# E17-PDU-6-LOAD_2.net
KiCad netlist of a schematic drawn in Altium Designer
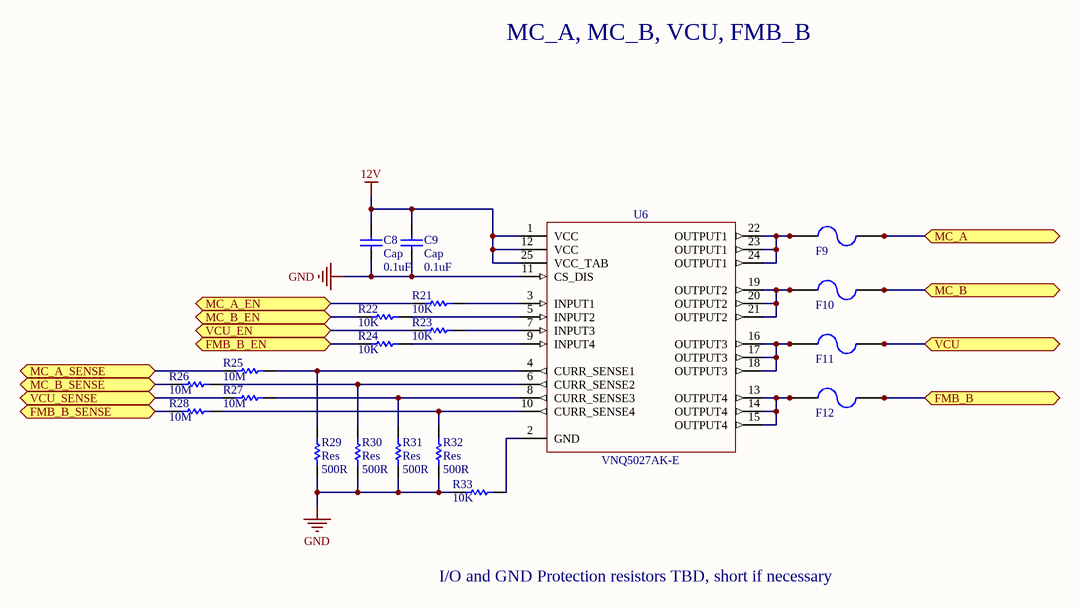
[diagram p0: E17-PDU-6-LOAD_2.SchDoc]

(export (version "E")
  (design (tool "Eeschema 10.0.6"))
  (components
    (comp (ref "C8")
      (value "Cap")
      (footprint "C0805")
      (description "Capacitor")
      (fields (field (name "ALTIUM_VALUE") "0.1uF") (field (name "PUBLISHER") "Altium Limited"))
      (libsource (lib "Capacitors") (part "Cap"))
    )
    (comp (ref "C9")
      (value "Cap")
      (footprint "C0805")
      (description "Capacitor")
      (fields (field (name "ALTIUM_VALUE") "0.1uF") (field (name "PUBLISHER") "Altium Limited"))
      (libsource (lib "Capacitors") (part "Cap"))
    )
    (comp (ref "F9")
      (value "BK-6013")
      (footprint "BK-6013")
      (description "FUSE HOLDER BLADE PCB")
      (libsource (lib "Fuses") (part "BK-6013"))
    )
    (comp (ref "F10")
      (value "BK-6013")
      (footprint "BK-6013")
      (description "FUSE HOLDER BLADE PCB")
      (libsource (lib "Fuses") (part "BK-6013"))
    )
    (comp (ref "F11")
      (value "BK-6013")
      (footprint "BK-6013")
      (description "FUSE HOLDER BLADE PCB")
      (libsource (lib "Fuses") (part "BK-6013"))
    )
    (comp (ref "F12")
      (value "BK-6013")
      (footprint "BK-6013")
      (description "FUSE HOLDER BLADE PCB")
      (libsource (lib "Fuses") (part "BK-6013"))
    )
    (comp (ref "R21")
      (value "10K")
      (footprint "2012[0805]")
      (description "Surface Mount Resistor")
      (fields (field (name "Comment") "Res") (field (name "PUBLISHER") "Altium Limited"))
      (libsource (lib "Resistors") (part "Res"))
    )
    (comp (ref "R22")
      (value "10K")
      (footprint "2012[0805]")
      (description "Surface Mount Resistor")
      (fields (field (name "Comment") "Res") (field (name "PUBLISHER") "Altium Limited"))
      (libsource (lib "Resistors") (part "Res"))
    )
    (comp (ref "R23")
      (value "10K")
      (footprint "2012[0805]")
      (description "Surface Mount Resistor")
      (fields (field (name "Comment") "Res") (field (name "PUBLISHER") "Altium Limited"))
      (libsource (lib "Resistors") (part "Res"))
    )
    (comp (ref "R24")
      (value "10K")
      (footprint "2012[0805]")
      (description "Surface Mount Resistor")
      (fields (field (name "Comment") "Res") (field (name "PUBLISHER") "Altium Limited"))
      (libsource (lib "Resistors") (part "Res"))
    )
    (comp (ref "R25")
      (value "10M")
      (footprint "2012[0805]")
      (description "Surface Mount Resistor")
      (fields (field (name "Comment") "Res") (field (name "PUBLISHER") "Altium Limited"))
      (libsource (lib "Resistors") (part "Res"))
    )
    (comp (ref "R26")
      (value "10M")
      (footprint "2012[0805]")
      (description "Surface Mount Resistor")
      (fields (field (name "Comment") "Res") (field (name "PUBLISHER") "Altium Limited"))
      (libsource (lib "Resistors") (part "Res"))
    )
    (comp (ref "R27")
      (value "10M")
      (footprint "2012[0805]")
      (description "Surface Mount Resistor")
      (fields (field (name "Comment") "Res") (field (name "PUBLISHER") "Altium Limited"))
      (libsource (lib "Resistors") (part "Res"))
    )
    (comp (ref "R28")
      (value "10M")
      (footprint "2012[0805]")
      (description "Surface Mount Resistor")
      (fields (field (name "Comment") "Res") (field (name "PUBLISHER") "Altium Limited"))
      (libsource (lib "Resistors") (part "Res"))
    )
    (comp (ref "R29")
      (value "Res")
      (footprint "2012[0805]")
      (description "Surface Mount Resistor")
      (fields (field (name "ALTIUM_VALUE") "500R") (field (name "PUBLISHER") "Altium Limited"))
      (libsource (lib "Resistors") (part "Res"))
    )
    (comp (ref "R30")
      (value "Res")
      (footprint "2012[0805]")
      (description "Surface Mount Resistor")
      (fields (field (name "ALTIUM_VALUE") "500R") (field (name "PUBLISHER") "Altium Limited"))
      (libsource (lib "Resistors") (part "Res"))
    )
    (comp (ref "R31")
      (value "Res")
      (footprint "2012[0805]")
      (description "Surface Mount Resistor")
      (fields (field (name "ALTIUM_VALUE") "500R") (field (name "PUBLISHER") "Altium Limited"))
      (libsource (lib "Resistors") (part "Res"))
    )
    (comp (ref "R32")
      (value "Res")
      (footprint "2012[0805]")
      (description "Surface Mount Resistor")
      (fields (field (name "ALTIUM_VALUE") "500R") (field (name "PUBLISHER") "Altium Limited"))
      (libsource (lib "Resistors") (part "Res"))
    )
    (comp (ref "R33")
      (value "10K")
      (footprint "2012[0805]")
      (description "Surface Mount Resistor")
      (fields (field (name "Comment") "Res") (field (name "PUBLISHER") "Altium Limited"))
      (libsource (lib "Resistors") (part "Res"))
    )
    (comp (ref "U6")
      (value "U_VNQ5027AK-E")
      (footprint "PowerSSO-24")
      (description "LOAD CHANNEL HIGH SIDE 42 A 4 Channel")
      (fields (field (name "MFG") "STmicroelectronics") (field (name "MFG_PN") "VNQ5027AK-E"))
      (libsource (lib "Transistors") (part "U_VNQ5027AK-E"))
    )
  )
  (nets
    (net (code "1") (name "/FMB_B") (class "Default")
      (node (ref "F12") (pin "3") (pinfunction "3_3") (pintype "passive"))
      (node (ref "F12") (pin "4") (pinfunction "4_4") (pintype "passive"))
    )
    (net (code "2") (name "/FMB_B_EN") (class "Default")
      (node (ref "R24") (pin "2") (pinfunction "2_2") (pintype "passive"))
    )
    (net (code "3") (name "/FMB_B_SENSE") (class "Default")
      (node (ref "R28") (pin "2") (pinfunction "2_2") (pintype "passive"))
    )
    (net (code "4") (name "/MC_A") (class "Default")
      (node (ref "F9") (pin "3") (pinfunction "3_3") (pintype "passive"))
      (node (ref "F9") (pin "4") (pinfunction "4_4") (pintype "passive"))
    )
    (net (code "5") (name "/MC_A_EN") (class "Default")
      (node (ref "R21") (pin "2") (pinfunction "2_2") (pintype "passive"))
    )
    (net (code "6") (name "/MC_A_SENSE") (class "Default")
      (node (ref "R25") (pin "2") (pinfunction "2_2") (pintype "passive"))
    )
    (net (code "7") (name "/MC_B") (class "Default")
      (node (ref "F10") (pin "3") (pinfunction "3_3") (pintype "passive"))
      (node (ref "F10") (pin "4") (pinfunction "4_4") (pintype "passive"))
    )
    (net (code "8") (name "/MC_B_EN") (class "Default")
      (node (ref "R22") (pin "2") (pinfunction "2_2") (pintype "passive"))
    )
    (net (code "9") (name "/MC_B_SENSE") (class "Default")
      (node (ref "R26") (pin "2") (pinfunction "2_2") (pintype "passive"))
    )
    (net (code "10") (name "/VCU") (class "Default")
      (node (ref "F11") (pin "3") (pinfunction "3_3") (pintype "passive"))
      (node (ref "F11") (pin "4") (pinfunction "4_4") (pintype "passive"))
    )
    (net (code "11") (name "/VCU_EN") (class "Default")
      (node (ref "R23") (pin "2") (pinfunction "2_2") (pintype "passive"))
    )
    (net (code "12") (name "/VCU_SENSE") (class "Default")
      (node (ref "R27") (pin "2") (pinfunction "2_2") (pintype "passive"))
    )
    (net (code "13") (name "12V") (class "Default")
      (node (ref "C8") (pin "2") (pinfunction "2_2") (pintype "passive"))
      (node (ref "C9") (pin "2") (pinfunction "2_2") (pintype "passive"))
      (node (ref "U6") (pin "1") (pinfunction "VCC_1") (pintype "power_in"))
      (node (ref "U6") (pin "12") (pinfunction "VCC_12") (pintype "power_in"))
      (node (ref "U6") (pin "25") (pinfunction "VCC_TAB_25") (pintype "power_in"))
    )
    (net (code "14") (name "GND") (class "Default")
      (node (ref "C8") (pin "1") (pinfunction "1_1") (pintype "passive"))
      (node (ref "C9") (pin "1") (pinfunction "1_1") (pintype "passive"))
      (node (ref "R29") (pin "1") (pinfunction "1_1") (pintype "passive"))
      (node (ref "R30") (pin "1") (pinfunction "1_1") (pintype "passive"))
      (node (ref "R31") (pin "1") (pinfunction "1_1") (pintype "passive"))
      (node (ref "R32") (pin "1") (pinfunction "1_1") (pintype "passive"))
      (node (ref "R33") (pin "2") (pinfunction "2_2") (pintype "passive"))
      (node (ref "U6") (pin "11") (pinfunction "CS_DIS_11") (pintype "input"))
    )
    (net (code "15") (name "Net-(F9-Pad1)") (class "Default")
      (node (ref "F9") (pin "1") (pinfunction "1_1") (pintype "passive"))
      (node (ref "F9") (pin "2") (pinfunction "2_2") (pintype "passive"))
      (node (ref "U6") (pin "22") (pinfunction "OUTPUT1_22") (pintype "output"))
      (node (ref "U6") (pin "23") (pinfunction "OUTPUT1_23") (pintype "output"))
      (node (ref "U6") (pin "24") (pinfunction "OUTPUT1_24") (pintype "output"))
    )
    (net (code "16") (name "Net-(F10-Pad1)") (class "Default")
      (node (ref "F10") (pin "1") (pinfunction "1_1") (pintype "passive"))
      (node (ref "F10") (pin "2") (pinfunction "2_2") (pintype "passive"))
      (node (ref "U6") (pin "19") (pinfunction "OUTPUT2_19") (pintype "output"))
      (node (ref "U6") (pin "20") (pinfunction "OUTPUT2_20") (pintype "output"))
      (node (ref "U6") (pin "21") (pinfunction "OUTPUT2_21") (pintype "output"))
    )
    (net (code "17") (name "Net-(F11-Pad1)") (class "Default")
      (node (ref "F11") (pin "1") (pinfunction "1_1") (pintype "passive"))
      (node (ref "F11") (pin "2") (pinfunction "2_2") (pintype "passive"))
      (node (ref "U6") (pin "16") (pinfunction "OUTPUT3_16") (pintype "output"))
      (node (ref "U6") (pin "17") (pinfunction "OUTPUT3_17") (pintype "output"))
      (node (ref "U6") (pin "18") (pinfunction "OUTPUT3_18") (pintype "output"))
    )
    (net (code "18") (name "Net-(F12-Pad1)") (class "Default")
      (node (ref "F12") (pin "1") (pinfunction "1_1") (pintype "passive"))
      (node (ref "F12") (pin "2") (pinfunction "2_2") (pintype "passive"))
      (node (ref "U6") (pin "13") (pinfunction "OUTPUT4_13") (pintype "output"))
      (node (ref "U6") (pin "14") (pinfunction "OUTPUT4_14") (pintype "output"))
      (node (ref "U6") (pin "15") (pinfunction "OUTPUT4_15") (pintype "output"))
    )
    (net (code "19") (name "Net-(U6-CURR_SENSE1)") (class "Default")
      (node (ref "R25") (pin "1") (pinfunction "1_1") (pintype "passive"))
      (node (ref "R29") (pin "2") (pinfunction "2_2") (pintype "passive"))
      (node (ref "U6") (pin "4") (pinfunction "CURR_SENSE1_4") (pintype "output"))
    )
    (net (code "20") (name "Net-(U6-CURR_SENSE2)") (class "Default")
      (node (ref "R26") (pin "1") (pinfunction "1_1") (pintype "passive"))
      (node (ref "R30") (pin "2") (pinfunction "2_2") (pintype "passive"))
      (node (ref "U6") (pin "6") (pinfunction "CURR_SENSE2_6") (pintype "output"))
    )
    (net (code "21") (name "Net-(U6-CURR_SENSE3)") (class "Default")
      (node (ref "R27") (pin "1") (pinfunction "1_1") (pintype "passive"))
      (node (ref "R31") (pin "2") (pinfunction "2_2") (pintype "passive"))
      (node (ref "U6") (pin "8") (pinfunction "CURR_SENSE3_8") (pintype "output"))
    )
    (net (code "22") (name "Net-(U6-CURR_SENSE4)") (class "Default")
      (node (ref "R28") (pin "1") (pinfunction "1_1") (pintype "passive"))
      (node (ref "R32") (pin "2") (pinfunction "2_2") (pintype "passive"))
      (node (ref "U6") (pin "10") (pinfunction "CURR_SENSE4_10") (pintype "output"))
    )
    (net (code "23") (name "Net-(U6-GND)") (class "Default")
      (node (ref "R33") (pin "1") (pinfunction "1_1") (pintype "passive"))
      (node (ref "U6") (pin "2") (pinfunction "GND_2") (pintype "power_in"))
    )
    (net (code "24") (name "Net-(U6-INPUT1)") (class "Default")
      (node (ref "R21") (pin "1") (pinfunction "1_1") (pintype "passive"))
      (node (ref "U6") (pin "3") (pinfunction "INPUT1_3") (pintype "input"))
    )
    (net (code "25") (name "Net-(U6-INPUT2)") (class "Default")
      (node (ref "R22") (pin "1") (pinfunction "1_1") (pintype "passive"))
      (node (ref "U6") (pin "5") (pinfunction "INPUT2_5") (pintype "input"))
    )
    (net (code "26") (name "Net-(U6-INPUT3)") (class "Default")
      (node (ref "R23") (pin "1") (pinfunction "1_1") (pintype "passive"))
      (node (ref "U6") (pin "7") (pinfunction "INPUT3_7") (pintype "input"))
    )
    (net (code "27") (name "Net-(U6-INPUT4)") (class "Default")
      (node (ref "R24") (pin "1") (pinfunction "1_1") (pintype "passive"))
      (node (ref "U6") (pin "9") (pinfunction "INPUT4_9") (pintype "input"))
    )
  )
)
